# Tubes.net
KiCad netlist of a schematic drawn in Altium Designer
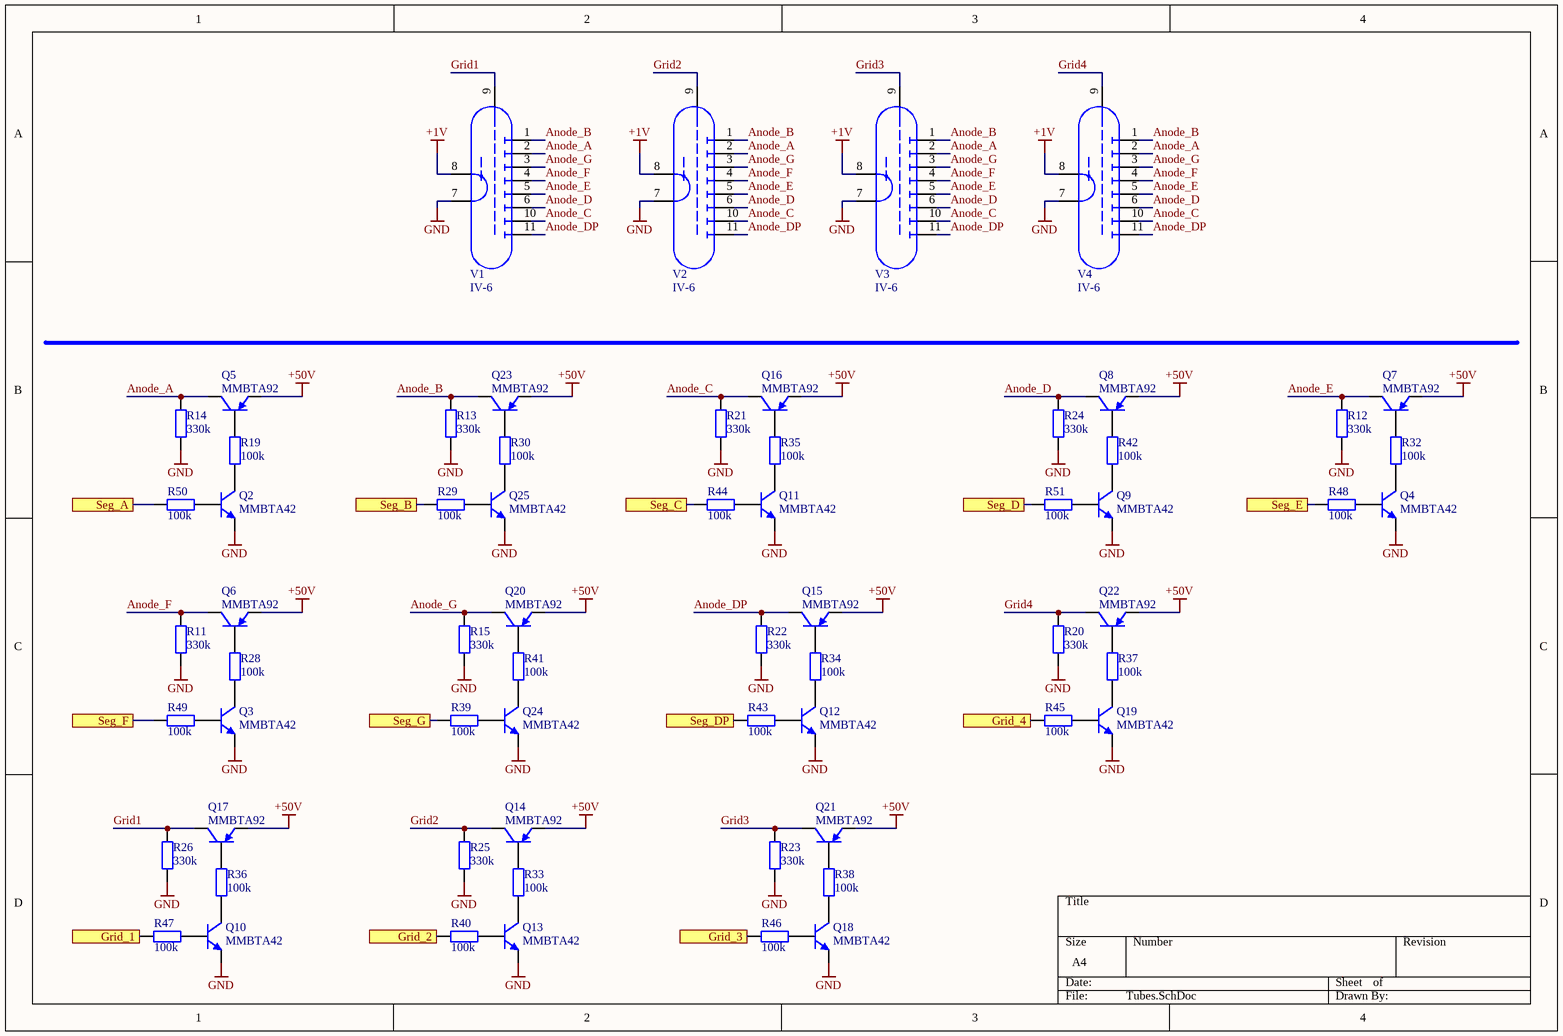
[diagram p0: Tubes.SchDoc]

(export (version "E")
  (design (tool "Eeschema 10.0.6"))
  (components
    (comp (ref "Q2")
      (value "MMBTA42")
      (footprint "SOT-23_N")
      (description "NPN Bipolar Transistor")
      (fields (field (name "PUBLISHER") "Altium Limited"))
      (libsource (lib "Lib_VFD_Clock") (part "NPN"))
    )
    (comp (ref "Q3")
      (value "MMBTA42")
      (footprint "SOT-23_N")
      (description "NPN Bipolar Transistor")
      (fields (field (name "PUBLISHER") "Altium Limited"))
      (libsource (lib "Lib_VFD_Clock") (part "NPN"))
    )
    (comp (ref "Q4")
      (value "MMBTA42")
      (footprint "SOT-23_N")
      (description "NPN Bipolar Transistor")
      (fields (field (name "PUBLISHER") "Altium Limited"))
      (libsource (lib "Lib_VFD_Clock") (part "NPN"))
    )
    (comp (ref "Q5")
      (value "MMBTA92")
      (footprint "SOT-23B_N")
      (description "PNP Bipolar Transistor")
      (fields (field (name "PUBLISHER") "Altium Limited"))
      (libsource (lib "Lib_VFD_Clock") (part "PNP"))
    )
    (comp (ref "Q6")
      (value "MMBTA92")
      (footprint "SOT-23B_N")
      (description "PNP Bipolar Transistor")
      (fields (field (name "PUBLISHER") "Altium Limited"))
      (libsource (lib "Lib_VFD_Clock") (part "PNP"))
    )
    (comp (ref "Q7")
      (value "MMBTA92")
      (footprint "SOT-23B_N")
      (description "PNP Bipolar Transistor")
      (fields (field (name "PUBLISHER") "Altium Limited"))
      (libsource (lib "Lib_VFD_Clock") (part "PNP"))
    )
    (comp (ref "Q8")
      (value "MMBTA92")
      (footprint "SOT-23B_N")
      (description "PNP Bipolar Transistor")
      (fields (field (name "PUBLISHER") "Altium Limited"))
      (libsource (lib "Lib_VFD_Clock") (part "PNP"))
    )
    (comp (ref "Q9")
      (value "MMBTA42")
      (footprint "SOT-23_N")
      (description "NPN Bipolar Transistor")
      (fields (field (name "PUBLISHER") "Altium Limited"))
      (libsource (lib "Lib_VFD_Clock") (part "NPN"))
    )
    (comp (ref "Q10")
      (value "MMBTA42")
      (footprint "SOT-23_N")
      (description "NPN Bipolar Transistor")
      (fields (field (name "PUBLISHER") "Altium Limited"))
      (libsource (lib "Lib_VFD_Clock") (part "NPN"))
    )
    (comp (ref "Q11")
      (value "MMBTA42")
      (footprint "SOT-23_N")
      (description "NPN Bipolar Transistor")
      (fields (field (name "PUBLISHER") "Altium Limited"))
      (libsource (lib "Lib_VFD_Clock") (part "NPN"))
    )
    (comp (ref "Q12")
      (value "MMBTA42")
      (footprint "SOT-23_N")
      (description "NPN Bipolar Transistor")
      (fields (field (name "PUBLISHER") "Altium Limited"))
      (libsource (lib "Lib_VFD_Clock") (part "NPN"))
    )
    (comp (ref "Q13")
      (value "MMBTA42")
      (footprint "SOT-23_N")
      (description "NPN Bipolar Transistor")
      (fields (field (name "PUBLISHER") "Altium Limited"))
      (libsource (lib "Lib_VFD_Clock") (part "NPN"))
    )
    (comp (ref "Q14")
      (value "MMBTA92")
      (footprint "SOT-23B_N")
      (description "PNP Bipolar Transistor")
      (fields (field (name "PUBLISHER") "Altium Limited"))
      (libsource (lib "Lib_VFD_Clock") (part "PNP"))
    )
    (comp (ref "Q15")
      (value "MMBTA92")
      (footprint "SOT-23B_N")
      (description "PNP Bipolar Transistor")
      (fields (field (name "PUBLISHER") "Altium Limited"))
      (libsource (lib "Lib_VFD_Clock") (part "PNP"))
    )
    (comp (ref "Q16")
      (value "MMBTA92")
      (footprint "SOT-23B_N")
      (description "PNP Bipolar Transistor")
      (fields (field (name "PUBLISHER") "Altium Limited"))
      (libsource (lib "Lib_VFD_Clock") (part "PNP"))
    )
    (comp (ref "Q17")
      (value "MMBTA92")
      (footprint "SOT-23B_N")
      (description "PNP Bipolar Transistor")
      (fields (field (name "PUBLISHER") "Altium Limited"))
      (libsource (lib "Lib_VFD_Clock") (part "PNP"))
    )
    (comp (ref "Q18")
      (value "MMBTA42")
      (footprint "SOT-23_N")
      (description "NPN Bipolar Transistor")
      (fields (field (name "PUBLISHER") "Altium Limited"))
      (libsource (lib "Lib_VFD_Clock") (part "NPN"))
    )
    (comp (ref "Q19")
      (value "MMBTA42")
      (footprint "SOT-23_N")
      (description "NPN Bipolar Transistor")
      (fields (field (name "PUBLISHER") "Altium Limited"))
      (libsource (lib "Lib_VFD_Clock") (part "NPN"))
    )
    (comp (ref "Q20")
      (value "MMBTA92")
      (footprint "SOT-23B_N")
      (description "PNP Bipolar Transistor")
      (fields (field (name "PUBLISHER") "Altium Limited"))
      (libsource (lib "Lib_VFD_Clock") (part "PNP"))
    )
    (comp (ref "Q21")
      (value "MMBTA92")
      (footprint "SOT-23B_N")
      (description "PNP Bipolar Transistor")
      (fields (field (name "PUBLISHER") "Altium Limited"))
      (libsource (lib "Lib_VFD_Clock") (part "PNP"))
    )
    (comp (ref "Q22")
      (value "MMBTA92")
      (footprint "SOT-23B_N")
      (description "PNP Bipolar Transistor")
      (fields (field (name "PUBLISHER") "Altium Limited"))
      (libsource (lib "Lib_VFD_Clock") (part "PNP"))
    )
    (comp (ref "Q23")
      (value "MMBTA92")
      (footprint "SOT-23B_N")
      (description "PNP Bipolar Transistor")
      (fields (field (name "PUBLISHER") "Altium Limited"))
      (libsource (lib "Lib_VFD_Clock") (part "PNP"))
    )
    (comp (ref "Q24")
      (value "MMBTA42")
      (footprint "SOT-23_N")
      (description "NPN Bipolar Transistor")
      (fields (field (name "PUBLISHER") "Altium Limited"))
      (libsource (lib "Lib_VFD_Clock") (part "NPN"))
    )
    (comp (ref "Q25")
      (value "MMBTA42")
      (footprint "SOT-23_N")
      (description "NPN Bipolar Transistor")
      (fields (field (name "PUBLISHER") "Altium Limited"))
      (libsource (lib "Lib_VFD_Clock") (part "NPN"))
    )
    (comp (ref "R11")
      (value "330k")
      (footprint "Lib_VFD_Clock:RES 0805_2012")
      (description "Resistor")
      (fields (field (name "PUBLISHER") "Altium Limited"))
      (libsource (lib "") (part "Res2_1"))
    )
    (comp (ref "R12")
      (value "330k")
      (footprint "Lib_VFD_Clock:RES 0805_2012")
      (description "Resistor")
      (fields (field (name "PUBLISHER") "Altium Limited"))
      (libsource (lib "") (part "Res2_1"))
    )
    (comp (ref "R13")
      (value "330k")
      (footprint "Lib_VFD_Clock:RES 0805_2012")
      (description "Resistor")
      (fields (field (name "PUBLISHER") "Altium Limited"))
      (libsource (lib "") (part "Res2_1"))
    )
    (comp (ref "R14")
      (value "330k")
      (footprint "Lib_VFD_Clock:RES 0805_2012")
      (description "Resistor")
      (fields (field (name "PUBLISHER") "Altium Limited"))
      (libsource (lib "") (part "Res2_1"))
    )
    (comp (ref "R15")
      (value "330k")
      (footprint "Lib_VFD_Clock:RES 0805_2012")
      (description "Resistor")
      (fields (field (name "PUBLISHER") "Altium Limited"))
      (libsource (lib "") (part "Res2_1"))
    )
    (comp (ref "R19")
      (value "100k")
      (footprint "Miscellaneous Devices:J1-0603")
      (description "Resistor")
      (fields (field (name "PUBLISHER") "Altium Limited"))
      (libsource (lib "") (part "Res2_1"))
    )
    (comp (ref "R20")
      (value "330k")
      (footprint "Lib_VFD_Clock:RES 0805_2012")
      (description "Resistor")
      (fields (field (name "PUBLISHER") "Altium Limited"))
      (libsource (lib "") (part "Res2_1"))
    )
    (comp (ref "R21")
      (value "330k")
      (footprint "Lib_VFD_Clock:RES 0805_2012")
      (description "Resistor")
      (fields (field (name "PUBLISHER") "Altium Limited"))
      (libsource (lib "") (part "Res2_1"))
    )
    (comp (ref "R22")
      (value "330k")
      (footprint "Lib_VFD_Clock:RES 0805_2012")
      (description "Resistor")
      (fields (field (name "PUBLISHER") "Altium Limited"))
      (libsource (lib "") (part "Res2_1"))
    )
    (comp (ref "R23")
      (value "330k")
      (footprint "Lib_VFD_Clock:RES 0805_2012")
      (description "Resistor")
      (fields (field (name "PUBLISHER") "Altium Limited"))
      (libsource (lib "") (part "Res2_1"))
    )
    (comp (ref "R24")
      (value "330k")
      (footprint "Lib_VFD_Clock:RES 0805_2012")
      (description "Resistor")
      (fields (field (name "PUBLISHER") "Altium Limited"))
      (libsource (lib "") (part "Res2_1"))
    )
    (comp (ref "R25")
      (value "330k")
      (footprint "Lib_VFD_Clock:RES 0805_2012")
      (description "Resistor")
      (fields (field (name "PUBLISHER") "Altium Limited"))
      (libsource (lib "") (part "Res2_1"))
    )
    (comp (ref "R26")
      (value "330k")
      (footprint "Lib_VFD_Clock:RES 0805_2012")
      (description "Resistor")
      (fields (field (name "PUBLISHER") "Altium Limited"))
      (libsource (lib "") (part "Res2_1"))
    )
    (comp (ref "R28")
      (value "100k")
      (footprint "Miscellaneous Devices:J1-0603")
      (description "Resistor")
      (fields (field (name "PUBLISHER") "Altium Limited"))
      (libsource (lib "") (part "Res2_1"))
    )
    (comp (ref "R29")
      (value "100k")
      (footprint "Miscellaneous Devices:J1-0603")
      (description "Resistor")
      (fields (field (name "PUBLISHER") "Altium Limited"))
      (libsource (lib "Miscellaneous Devices") (part "Res2"))
    )
    (comp (ref "R30")
      (value "100k")
      (footprint "Miscellaneous Devices:J1-0603")
      (description "Resistor")
      (fields (field (name "PUBLISHER") "Altium Limited"))
      (libsource (lib "") (part "Res2_1"))
    )
    (comp (ref "R32")
      (value "100k")
      (footprint "Miscellaneous Devices:J1-0603")
      (description "Resistor")
      (fields (field (name "PUBLISHER") "Altium Limited"))
      (libsource (lib "") (part "Res2_1"))
    )
    (comp (ref "R33")
      (value "100k")
      (footprint "Miscellaneous Devices:J1-0603")
      (description "Resistor")
      (fields (field (name "PUBLISHER") "Altium Limited"))
      (libsource (lib "") (part "Res2_1"))
    )
    (comp (ref "R34")
      (value "100k")
      (footprint "Miscellaneous Devices:J1-0603")
      (description "Resistor")
      (fields (field (name "PUBLISHER") "Altium Limited"))
      (libsource (lib "") (part "Res2_1"))
    )
    (comp (ref "R35")
      (value "100k")
      (footprint "Miscellaneous Devices:J1-0603")
      (description "Resistor")
      (fields (field (name "PUBLISHER") "Altium Limited"))
      (libsource (lib "") (part "Res2_1"))
    )
    (comp (ref "R36")
      (value "100k")
      (footprint "Miscellaneous Devices:J1-0603")
      (description "Resistor")
      (fields (field (name "PUBLISHER") "Altium Limited"))
      (libsource (lib "") (part "Res2_1"))
    )
    (comp (ref "R37")
      (value "100k")
      (footprint "Miscellaneous Devices:J1-0603")
      (description "Resistor")
      (fields (field (name "PUBLISHER") "Altium Limited"))
      (libsource (lib "") (part "Res2_1"))
    )
    (comp (ref "R38")
      (value "100k")
      (footprint "Miscellaneous Devices:J1-0603")
      (description "Resistor")
      (fields (field (name "PUBLISHER") "Altium Limited"))
      (libsource (lib "") (part "Res2_1"))
    )
    (comp (ref "R39")
      (value "100k")
      (footprint "Miscellaneous Devices:J1-0603")
      (description "Resistor")
      (fields (field (name "PUBLISHER") "Altium Limited"))
      (libsource (lib "Miscellaneous Devices") (part "Res2"))
    )
    (comp (ref "R40")
      (value "100k")
      (footprint "Miscellaneous Devices:J1-0603")
      (description "Resistor")
      (fields (field (name "PUBLISHER") "Altium Limited"))
      (libsource (lib "Miscellaneous Devices") (part "Res2"))
    )
    (comp (ref "R41")
      (value "100k")
      (footprint "Miscellaneous Devices:J1-0603")
      (description "Resistor")
      (fields (field (name "PUBLISHER") "Altium Limited"))
      (libsource (lib "") (part "Res2_1"))
    )
    (comp (ref "R42")
      (value "100k")
      (footprint "Miscellaneous Devices:J1-0603")
      (description "Resistor")
      (fields (field (name "PUBLISHER") "Altium Limited"))
      (libsource (lib "") (part "Res2_1"))
    )
    (comp (ref "R43")
      (value "100k")
      (footprint "Miscellaneous Devices:J1-0603")
      (description "Resistor")
      (fields (field (name "PUBLISHER") "Altium Limited"))
      (libsource (lib "Miscellaneous Devices") (part "Res2"))
    )
    (comp (ref "R44")
      (value "100k")
      (footprint "Miscellaneous Devices:J1-0603")
      (description "Resistor")
      (fields (field (name "PUBLISHER") "Altium Limited"))
      (libsource (lib "Miscellaneous Devices") (part "Res2"))
    )
    (comp (ref "R45")
      (value "100k")
      (footprint "Miscellaneous Devices:J1-0603")
      (description "Resistor")
      (fields (field (name "PUBLISHER") "Altium Limited"))
      (libsource (lib "Miscellaneous Devices") (part "Res2"))
    )
    (comp (ref "R46")
      (value "100k")
      (footprint "Miscellaneous Devices:J1-0603")
      (description "Resistor")
      (fields (field (name "PUBLISHER") "Altium Limited"))
      (libsource (lib "Miscellaneous Devices") (part "Res2"))
    )
    (comp (ref "R47")
      (value "100k")
      (footprint "Miscellaneous Devices:J1-0603")
      (description "Resistor")
      (fields (field (name "PUBLISHER") "Altium Limited"))
      (libsource (lib "Miscellaneous Devices") (part "Res2"))
    )
    (comp (ref "R48")
      (value "100k")
      (footprint "Miscellaneous Devices:J1-0603")
      (description "Resistor")
      (fields (field (name "PUBLISHER") "Altium Limited"))
      (libsource (lib "Miscellaneous Devices") (part "Res2"))
    )
    (comp (ref "R49")
      (value "100k")
      (footprint "Miscellaneous Devices:J1-0603")
      (description "Resistor")
      (fields (field (name "PUBLISHER") "Altium Limited"))
      (libsource (lib "Miscellaneous Devices") (part "Res2"))
    )
    (comp (ref "R50")
      (value "100k")
      (footprint "Miscellaneous Devices:J1-0603")
      (description "Resistor")
      (fields (field (name "PUBLISHER") "Altium Limited"))
      (libsource (lib "Miscellaneous Devices") (part "Res2"))
    )
    (comp (ref "R51")
      (value "100k")
      (footprint "Miscellaneous Devices:J1-0603")
      (description "Resistor")
      (fields (field (name "PUBLISHER") "Altium Limited"))
      (libsource (lib "Miscellaneous Devices") (part "Res2"))
    )
    (comp (ref "V1") (value "IV-6") (footprint "IV-6") (libsource (lib "Lib_VFD_Clock") (part "IV-6")))
    (comp (ref "V2") (value "IV-6") (footprint "IV-6") (libsource (lib "Lib_VFD_Clock") (part "IV-6")))
    (comp (ref "V3") (value "IV-6") (footprint "IV-6") (libsource (lib "Lib_VFD_Clock") (part "IV-6")))
    (comp (ref "V4") (value "IV-6") (footprint "IV-6") (libsource (lib "Lib_VFD_Clock") (part "IV-6")))
  )
  (nets
    (net (code "1") (name "+1V") (class "Default")
      (node (ref "V1") (pin "8") (pinfunction "8_8") (pintype "passive"))
      (node (ref "V2") (pin "8") (pinfunction "8_8") (pintype "passive"))
      (node (ref "V3") (pin "8") (pinfunction "8_8") (pintype "passive"))
      (node (ref "V4") (pin "8") (pinfunction "8_8") (pintype "passive"))
    )
    (net (code "2") (name "+50V") (class "Default")
      (node (ref "Q14") (pin "3") (pinfunction "E_3") (pintype "passive"))
      (node (ref "Q15") (pin "3") (pinfunction "E_3") (pintype "passive"))
      (node (ref "Q16") (pin "3") (pinfunction "E_3") (pintype "passive"))
      (node (ref "Q17") (pin "3") (pinfunction "E_3") (pintype "passive"))
      (node (ref "Q20") (pin "3") (pinfunction "E_3") (pintype "passive"))
      (node (ref "Q21") (pin "3") (pinfunction "E_3") (pintype "passive"))
      (node (ref "Q22") (pin "3") (pinfunction "E_3") (pintype "passive"))
      (node (ref "Q23") (pin "3") (pinfunction "E_3") (pintype "passive"))
      (node (ref "Q5") (pin "3") (pinfunction "E_3") (pintype "passive"))
      (node (ref "Q6") (pin "3") (pinfunction "E_3") (pintype "passive"))
      (node (ref "Q7") (pin "3") (pinfunction "E_3") (pintype "passive"))
      (node (ref "Q8") (pin "3") (pinfunction "E_3") (pintype "passive"))
    )
    (net (code "3") (name "/Anode_A") (class "Default")
      (node (ref "Q5") (pin "1") (pinfunction "C_1") (pintype "passive"))
      (node (ref "R14") (pin "2") (pinfunction "2_2") (pintype "passive"))
      (node (ref "V1") (pin "2") (pinfunction "2_2") (pintype "passive"))
      (node (ref "V2") (pin "2") (pinfunction "2_2") (pintype "passive"))
      (node (ref "V3") (pin "2") (pinfunction "2_2") (pintype "passive"))
      (node (ref "V4") (pin "2") (pinfunction "2_2") (pintype "passive"))
    )
    (net (code "4") (name "/Anode_B") (class "Default")
      (node (ref "Q23") (pin "1") (pinfunction "C_1") (pintype "passive"))
      (node (ref "R13") (pin "2") (pinfunction "2_2") (pintype "passive"))
      (node (ref "V1") (pin "1") (pinfunction "1_1") (pintype "passive"))
      (node (ref "V2") (pin "1") (pinfunction "1_1") (pintype "passive"))
      (node (ref "V3") (pin "1") (pinfunction "1_1") (pintype "passive"))
      (node (ref "V4") (pin "1") (pinfunction "1_1") (pintype "passive"))
    )
    (net (code "5") (name "/Anode_C") (class "Default")
      (node (ref "Q16") (pin "1") (pinfunction "C_1") (pintype "passive"))
      (node (ref "R21") (pin "2") (pinfunction "2_2") (pintype "passive"))
      (node (ref "V1") (pin "10") (pinfunction "10_10") (pintype "passive"))
      (node (ref "V2") (pin "10") (pinfunction "10_10") (pintype "passive"))
      (node (ref "V3") (pin "10") (pinfunction "10_10") (pintype "passive"))
      (node (ref "V4") (pin "10") (pinfunction "10_10") (pintype "passive"))
    )
    (net (code "6") (name "/Anode_D") (class "Default")
      (node (ref "Q8") (pin "1") (pinfunction "C_1") (pintype "passive"))
      (node (ref "R24") (pin "2") (pinfunction "2_2") (pintype "passive"))
      (node (ref "V1") (pin "6") (pinfunction "6_6") (pintype "passive"))
      (node (ref "V2") (pin "6") (pinfunction "6_6") (pintype "passive"))
      (node (ref "V3") (pin "6") (pinfunction "6_6") (pintype "passive"))
      (node (ref "V4") (pin "6") (pinfunction "6_6") (pintype "passive"))
    )
    (net (code "7") (name "/Anode_DP") (class "Default")
      (node (ref "Q15") (pin "1") (pinfunction "C_1") (pintype "passive"))
      (node (ref "R22") (pin "2") (pinfunction "2_2") (pintype "passive"))
      (node (ref "V1") (pin "11") (pinfunction "11_11") (pintype "passive"))
      (node (ref "V2") (pin "11") (pinfunction "11_11") (pintype "passive"))
      (node (ref "V3") (pin "11") (pinfunction "11_11") (pintype "passive"))
      (node (ref "V4") (pin "11") (pinfunction "11_11") (pintype "passive"))
    )
    (net (code "8") (name "/Anode_E") (class "Default")
      (node (ref "Q7") (pin "1") (pinfunction "C_1") (pintype "passive"))
      (node (ref "R12") (pin "2") (pinfunction "2_2") (pintype "passive"))
      (node (ref "V1") (pin "5") (pinfunction "5_5") (pintype "passive"))
      (node (ref "V2") (pin "5") (pinfunction "5_5") (pintype "passive"))
      (node (ref "V3") (pin "5") (pinfunction "5_5") (pintype "passive"))
      (node (ref "V4") (pin "5") (pinfunction "5_5") (pintype "passive"))
    )
    (net (code "9") (name "/Anode_F") (class "Default")
      (node (ref "Q6") (pin "1") (pinfunction "C_1") (pintype "passive"))
      (node (ref "R11") (pin "2") (pinfunction "2_2") (pintype "passive"))
      (node (ref "V1") (pin "4") (pinfunction "4_4") (pintype "passive"))
      (node (ref "V2") (pin "4") (pinfunction "4_4") (pintype "passive"))
      (node (ref "V3") (pin "4") (pinfunction "4_4") (pintype "passive"))
      (node (ref "V4") (pin "4") (pinfunction "4_4") (pintype "passive"))
    )
    (net (code "10") (name "/Anode_G") (class "Default")
      (node (ref "Q20") (pin "1") (pinfunction "C_1") (pintype "passive"))
      (node (ref "R15") (pin "2") (pinfunction "2_2") (pintype "passive"))
      (node (ref "V1") (pin "3") (pinfunction "3_3") (pintype "passive"))
      (node (ref "V2") (pin "3") (pinfunction "3_3") (pintype "passive"))
      (node (ref "V3") (pin "3") (pinfunction "3_3") (pintype "passive"))
      (node (ref "V4") (pin "3") (pinfunction "3_3") (pintype "passive"))
    )
    (net (code "11") (name "/Grid1") (class "Default")
      (node (ref "Q17") (pin "1") (pinfunction "C_1") (pintype "passive"))
      (node (ref "R26") (pin "2") (pinfunction "2_2") (pintype "passive"))
      (node (ref "V1") (pin "9") (pinfunction "9_9") (pintype "passive"))
    )
    (net (code "12") (name "/Grid2") (class "Default")
      (node (ref "Q14") (pin "1") (pinfunction "C_1") (pintype "passive"))
      (node (ref "R25") (pin "2") (pinfunction "2_2") (pintype "passive"))
      (node (ref "V2") (pin "9") (pinfunction "9_9") (pintype "passive"))
    )
    (net (code "13") (name "/Grid3") (class "Default")
      (node (ref "Q21") (pin "1") (pinfunction "C_1") (pintype "passive"))
      (node (ref "R23") (pin "2") (pinfunction "2_2") (pintype "passive"))
      (node (ref "V3") (pin "9") (pinfunction "9_9") (pintype "passive"))
    )
    (net (code "14") (name "/Grid4") (class "Default")
      (node (ref "Q22") (pin "1") (pinfunction "C_1") (pintype "passive"))
      (node (ref "R20") (pin "2") (pinfunction "2_2") (pintype "passive"))
      (node (ref "V4") (pin "9") (pinfunction "9_9") (pintype "passive"))
    )
    (net (code "15") (name "/Grid_1") (class "Default")
      (node (ref "R47") (pin "1") (pinfunction "1_1") (pintype "passive"))
    )
    (net (code "16") (name "/Grid_2") (class "Default")
      (node (ref "R40") (pin "1") (pinfunction "1_1") (pintype "passive"))
    )
    (net (code "17") (name "/Grid_3") (class "Default")
      (node (ref "R46") (pin "1") (pinfunction "1_1") (pintype "passive"))
    )
    (net (code "18") (name "/Grid_4") (class "Default")
      (node (ref "R45") (pin "1") (pinfunction "1_1") (pintype "passive"))
    )
    (net (code "19") (name "/Seg_A") (class "Default")
      (node (ref "R50") (pin "1") (pinfunction "1_1") (pintype "passive"))
    )
    (net (code "20") (name "/Seg_B") (class "Default")
      (node (ref "R29") (pin "1") (pinfunction "1_1") (pintype "passive"))
    )
    (net (code "21") (name "/Seg_C") (class "Default")
      (node (ref "R44") (pin "1") (pinfunction "1_1") (pintype "passive"))
    )
    (net (code "22") (name "/Seg_D") (class "Default")
      (node (ref "R51") (pin "1") (pinfunction "1_1") (pintype "passive"))
    )
    (net (code "23") (name "/Seg_DP") (class "Default")
      (node (ref "R43") (pin "1") (pinfunction "1_1") (pintype "passive"))
    )
    (net (code "24") (name "/Seg_E") (class "Default")
      (node (ref "R48") (pin "1") (pinfunction "1_1") (pintype "passive"))
    )
    (net (code "25") (name "/Seg_F") (class "Default")
      (node (ref "R49") (pin "1") (pinfunction "1_1") (pintype "passive"))
    )
    (net (code "26") (name "/Seg_G") (class "Default")
      (node (ref "R39") (pin "1") (pinfunction "1_1") (pintype "passive"))
    )
    (net (code "27") (name "GND") (class "Default")
      (node (ref "Q10") (pin "3") (pinfunction "E_3") (pintype "passive"))
      (node (ref "Q11") (pin "3") (pinfunction "E_3") (pintype "passive"))
      (node (ref "Q12") (pin "3") (pinfunction "E_3") (pintype "passive"))
      (node (ref "Q13") (pin "3") (pinfunction "E_3") (pintype "passive"))
      (node (ref "Q18") (pin "3") (pinfunction "E_3") (pintype "passive"))
      (node (ref "Q19") (pin "3") (pinfunction "E_3") (pintype "passive"))
      (node (ref "Q2") (pin "3") (pinfunction "E_3") (pintype "passive"))
      (node (ref "Q24") (pin "3") (pinfunction "E_3") (pintype "passive"))
      (node (ref "Q25") (pin "3") (pinfunction "E_3") (pintype "passive"))
      (node (ref "Q3") (pin "3") (pinfunction "E_3") (pintype "passive"))
      (node (ref "Q4") (pin "3") (pinfunction "E_3") (pintype "passive"))
      (node (ref "Q9") (pin "3") (pinfunction "E_3") (pintype "passive"))
      (node (ref "R11") (pin "1") (pinfunction "1_1") (pintype "passive"))
      (node (ref "R12") (pin "1") (pinfunction "1_1") (pintype "passive"))
      (node (ref "R13") (pin "1") (pinfunction "1_1") (pintype "passive"))
      (node (ref "R14") (pin "1") (pinfunction "1_1") (pintype "passive"))
      (node (ref "R15") (pin "1") (pinfunction "1_1") (pintype "passive"))
      (node (ref "R20") (pin "1") (pinfunction "1_1") (pintype "passive"))
      (node (ref "R21") (pin "1") (pinfunction "1_1") (pintype "passive"))
      (node (ref "R22") (pin "1") (pinfunction "1_1") (pintype "passive"))
      (node (ref "R23") (pin "1") (pinfunction "1_1") (pintype "passive"))
      (node (ref "R24") (pin "1") (pinfunction "1_1") (pintype "passive"))
      (node (ref "R25") (pin "1") (pinfunction "1_1") (pintype "passive"))
      (node (ref "R26") (pin "1") (pinfunction "1_1") (pintype "passive"))
      (node (ref "V1") (pin "7") (pinfunction "7_7") (pintype "passive"))
      (node (ref "V2") (pin "7") (pinfunction "7_7") (pintype "passive"))
      (node (ref "V3") (pin "7") (pinfunction "7_7") (pintype "passive"))
      (node (ref "V4") (pin "7") (pinfunction "7_7") (pintype "passive"))
    )
    (net (code "28") (name "Net-(Q2-B)") (class "Default")
      (node (ref "Q2") (pin "2") (pinfunction "B_2") (pintype "passive"))
      (node (ref "R50") (pin "2") (pinfunction "2_2") (pintype "passive"))
    )
    (net (code "29") (name "Net-(Q2-C)") (class "Default")
      (node (ref "Q2") (pin "1") (pinfunction "C_1") (pintype "passive"))
      (node (ref "R19") (pin "1") (pinfunction "1_1") (pintype "passive"))
    )
    (net (code "30") (name "Net-(Q3-B)") (class "Default")
      (node (ref "Q3") (pin "2") (pinfunction "B_2") (pintype "passive"))
      (node (ref "R49") (pin "2") (pinfunction "2_2") (pintype "passive"))
    )
    (net (code "31") (name "Net-(Q3-C)") (class "Default")
      (node (ref "Q3") (pin "1") (pinfunction "C_1") (pintype "passive"))
      (node (ref "R28") (pin "1") (pinfunction "1_1") (pintype "passive"))
    )
    (net (code "32") (name "Net-(Q4-B)") (class "Default")
      (node (ref "Q4") (pin "2") (pinfunction "B_2") (pintype "passive"))
      (node (ref "R48") (pin "2") (pinfunction "2_2") (pintype "passive"))
    )
    (net (code "33") (name "Net-(Q4-C)") (class "Default")
      (node (ref "Q4") (pin "1") (pinfunction "C_1") (pintype "passive"))
      (node (ref "R32") (pin "1") (pinfunction "1_1") (pintype "passive"))
    )
    (net (code "34") (name "Net-(Q5-B)") (class "Default")
      (node (ref "Q5") (pin "2") (pinfunction "B_2") (pintype "passive"))
      (node (ref "R19") (pin "2") (pinfunction "2_2") (pintype "passive"))
    )
    (net (code "35") (name "Net-(Q6-B)") (class "Default")
      (node (ref "Q6") (pin "2") (pinfunction "B_2") (pintype "passive"))
      (node (ref "R28") (pin "2") (pinfunction "2_2") (pintype "passive"))
    )
    (net (code "36") (name "Net-(Q7-B)") (class "Default")
      (node (ref "Q7") (pin "2") (pinfunction "B_2") (pintype "passive"))
      (node (ref "R32") (pin "2") (pinfunction "2_2") (pintype "passive"))
    )
    (net (code "37") (name "Net-(Q8-B)") (class "Default")
      (node (ref "Q8") (pin "2") (pinfunction "B_2") (pintype "passive"))
      (node (ref "R42") (pin "2") (pinfunction "2_2") (pintype "passive"))
    )
    (net (code "38") (name "Net-(Q9-B)") (class "Default")
      (node (ref "Q9") (pin "2") (pinfunction "B_2") (pintype "passive"))
      (node (ref "R51") (pin "2") (pinfunction "2_2") (pintype "passive"))
    )
    (net (code "39") (name "Net-(Q9-C)") (class "Default")
      (node (ref "Q9") (pin "1") (pinfunction "C_1") (pintype "passive"))
      (node (ref "R42") (pin "1") (pinfunction "1_1") (pintype "passive"))
    )
    (net (code "40") (name "Net-(Q10-B)") (class "Default")
      (node (ref "Q10") (pin "2") (pinfunction "B_2") (pintype "passive"))
      (node (ref "R47") (pin "2") (pinfunction "2_2") (pintype "passive"))
    )
    (net (code "41") (name "Net-(Q10-C)") (class "Default")
      (node (ref "Q10") (pin "1") (pinfunction "C_1") (pintype "passive"))
      (node (ref "R36") (pin "1") (pinfunction "1_1") (pintype "passive"))
    )
    (net (code "42") (name "Net-(Q11-B)") (class "Default")
      (node (ref "Q11") (pin "2") (pinfunction "B_2") (pintype "passive"))
      (node (ref "R44") (pin "2") (pinfunction "2_2") (pintype "passive"))
    )
    (net (code "43") (name "Net-(Q11-C)") (class "Default")
      (node (ref "Q11") (pin "1") (pinfunction "C_1") (pintype "passive"))
      (node (ref "R35") (pin "1") (pinfunction "1_1") (pintype "passive"))
    )
    (net (code "44") (name "Net-(Q12-B)") (class "Default")
      (node (ref "Q12") (pin "2") (pinfunction "B_2") (pintype "passive"))
      (node (ref "R43") (pin "2") (pinfunction "2_2") (pintype "passive"))
    )
    (net (code "45") (name "Net-(Q12-C)") (class "Default")
      (node (ref "Q12") (pin "1") (pinfunction "C_1") (pintype "passive"))
      (node (ref "R34") (pin "1") (pinfunction "1_1") (pintype "passive"))
    )
    (net (code "46") (name "Net-(Q13-B)") (class "Default")
      (node (ref "Q13") (pin "2") (pinfunction "B_2") (pintype "passive"))
      (node (ref "R40") (pin "2") (pinfunction "2_2") (pintype "passive"))
    )
    (net (code "47") (name "Net-(Q13-C)") (class "Default")
      (node (ref "Q13") (pin "1") (pinfunction "C_1") (pintype "passive"))
      (node (ref "R33") (pin "1") (pinfunction "1_1") (pintype "passive"))
    )
    (net (code "48") (name "Net-(Q14-B)") (class "Default")
      (node (ref "Q14") (pin "2") (pinfunction "B_2") (pintype "passive"))
      (node (ref "R33") (pin "2") (pinfunction "2_2") (pintype "passive"))
    )
    (net (code "49") (name "Net-(Q15-B)") (class "Default")
      (node (ref "Q15") (pin "2") (pinfunction "B_2") (pintype "passive"))
      (node (ref "R34") (pin "2") (pinfunction "2_2") (pintype "passive"))
    )
    (net (code "50") (name "Net-(Q16-B)") (class "Default")
      (node (ref "Q16") (pin "2") (pinfunction "B_2") (pintype "passive"))
      (node (ref "R35") (pin "2") (pinfunction "2_2") (pintype "passive"))
    )
    (net (code "51") (name "Net-(Q17-B)") (class "Default")
      (node (ref "Q17") (pin "2") (pinfunction "B_2") (pintype "passive"))
      (node (ref "R36") (pin "2") (pinfunction "2_2") (pintype "passive"))
    )
    (net (code "52") (name "Net-(Q18-B)") (class "Default")
      (node (ref "Q18") (pin "2") (pinfunction "B_2") (pintype "passive"))
      (node (ref "R46") (pin "2") (pinfunction "2_2") (pintype "passive"))
    )
    (net (code "53") (name "Net-(Q18-C)") (class "Default")
      (node (ref "Q18") (pin "1") (pinfunction "C_1") (pintype "passive"))
      (node (ref "R38") (pin "1") (pinfunction "1_1") (pintype "passive"))
    )
    (net (code "54") (name "Net-(Q19-B)") (class "Default")
      (node (ref "Q19") (pin "2") (pinfunction "B_2") (pintype "passive"))
      (node (ref "R45") (pin "2") (pinfunction "2_2") (pintype "passive"))
    )
    (net (code "55") (name "Net-(Q19-C)") (class "Default")
      (node (ref "Q19") (pin "1") (pinfunction "C_1") (pintype "passive"))
      (node (ref "R37") (pin "1") (pinfunction "1_1") (pintype "passive"))
    )
    (net (code "56") (name "Net-(Q20-B)") (class "Default")
      (node (ref "Q20") (pin "2") (pinfunction "B_2") (pintype "passive"))
      (node (ref "R41") (pin "2") (pinfunction "2_2") (pintype "passive"))
    )
    (net (code "57") (name "Net-(Q21-B)") (class "Default")
      (node (ref "Q21") (pin "2") (pinfunction "B_2") (pintype "passive"))
      (node (ref "R38") (pin "2") (pinfunction "2_2") (pintype "passive"))
    )
    (net (code "58") (name "Net-(Q22-B)") (class "Default")
      (node (ref "Q22") (pin "2") (pinfunction "B_2") (pintype "passive"))
      (node (ref "R37") (pin "2") (pinfunction "2_2") (pintype "passive"))
    )
    (net (code "59") (name "Net-(Q23-B)") (class "Default")
      (node (ref "Q23") (pin "2") (pinfunction "B_2") (pintype "passive"))
      (node (ref "R30") (pin "2") (pinfunction "2_2") (pintype "passive"))
    )
    (net (code "60") (name "Net-(Q24-B)") (class "Default")
      (node (ref "Q24") (pin "2") (pinfunction "B_2") (pintype "passive"))
      (node (ref "R39") (pin "2") (pinfunction "2_2") (pintype "passive"))
    )
    (net (code "61") (name "Net-(Q24-C)") (class "Default")
      (node (ref "Q24") (pin "1") (pinfunction "C_1") (pintype "passive"))
      (node (ref "R41") (pin "1") (pinfunction "1_1") (pintype "passive"))
    )
    (net (code "62") (name "Net-(Q25-B)") (class "Default")
      (node (ref "Q25") (pin "2") (pinfunction "B_2") (pintype "passive"))
      (node (ref "R29") (pin "2") (pinfunction "2_2") (pintype "passive"))
    )
    (net (code "63") (name "Net-(Q25-C)") (class "Default")
      (node (ref "Q25") (pin "1") (pinfunction "C_1") (pintype "passive"))
      (node (ref "R30") (pin "1") (pinfunction "1_1") (pintype "passive"))
    )
  )
)
